# 04_Temperature.net
KiCad netlist of a schematic drawn in Altium Designer
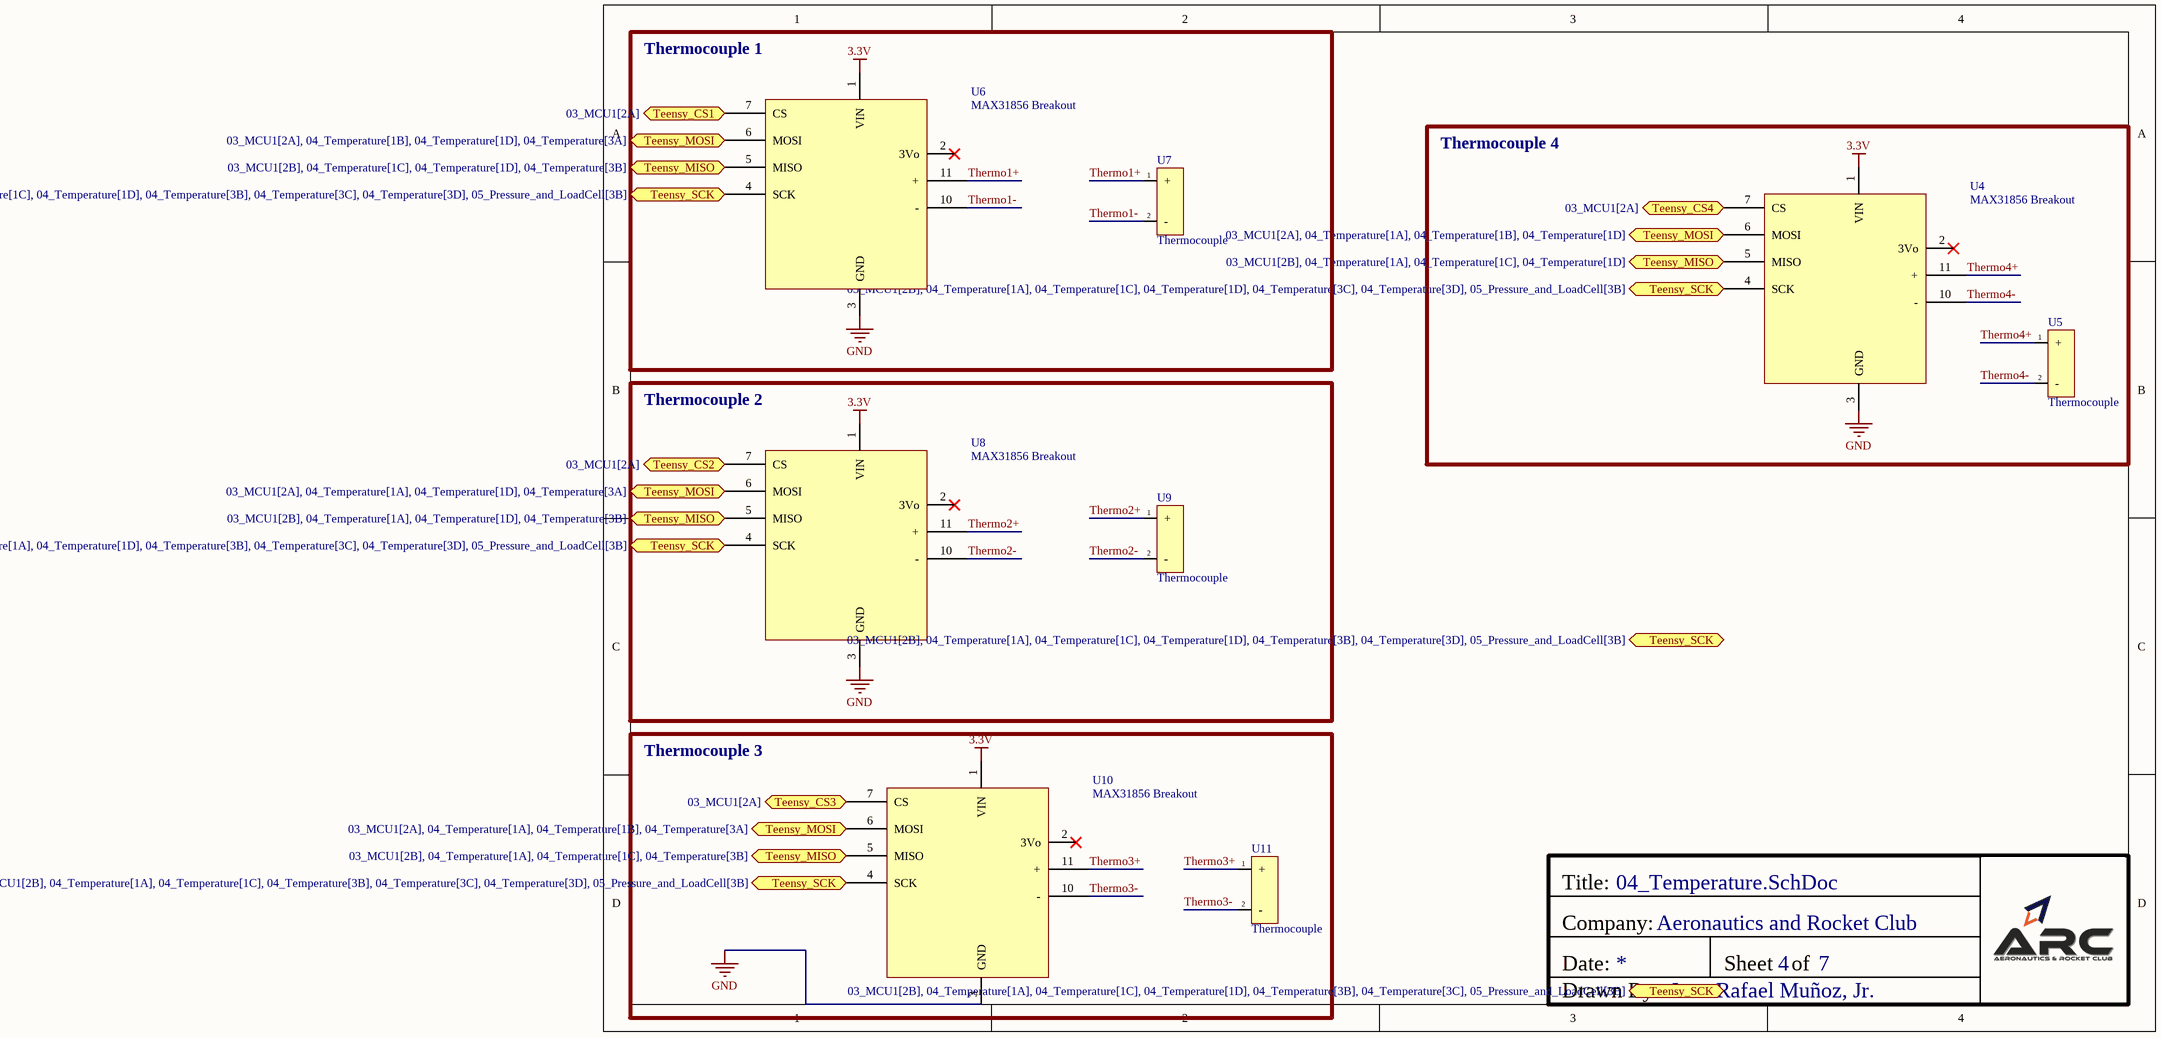
[diagram p0: 04_Temperature.SchDoc]

(export (version "E")
  (design (tool "Eeschema 10.0.6"))
  (components
    (comp (ref "U4")
      (value "MAX31856 Breakout")
      (footprint "MAX31856 Breakout")
      (libsource (lib "Ground Support_Schlib") (part "MAX31856 Breakout"))
    )
    (comp (ref "U5")
      (value "Thermocouple")
      (footprint "THERMOCOUPLE")
      (libsource (lib "Ground Support_Schlib") (part "Thermocouple"))
    )
    (comp (ref "U6")
      (value "MAX31856 Breakout")
      (footprint "MAX31856 Breakout")
      (libsource (lib "Ground Support_Schlib") (part "MAX31856 Breakout"))
    )
    (comp (ref "U7")
      (value "Thermocouple")
      (footprint "THERMOCOUPLE")
      (libsource (lib "Ground Support_Schlib") (part "Thermocouple"))
    )
    (comp (ref "U8")
      (value "MAX31856 Breakout")
      (footprint "MAX31856 Breakout")
      (libsource (lib "Ground Support_Schlib") (part "MAX31856 Breakout"))
    )
    (comp (ref "U9")
      (value "Thermocouple")
      (footprint "THERMOCOUPLE")
      (libsource (lib "Ground Support_Schlib") (part "Thermocouple"))
    )
    (comp (ref "U10")
      (value "MAX31856 Breakout")
      (footprint "MAX31856 Breakout")
      (libsource (lib "Ground Support_Schlib") (part "MAX31856 Breakout"))
    )
    (comp (ref "U11")
      (value "Thermocouple")
      (footprint "THERMOCOUPLE")
      (libsource (lib "Ground Support_Schlib") (part "Thermocouple"))
    )
  )
  (nets
    (net (code "1") (name "/Teensy_CS1") (class "Default")
      (node (ref "U6") (pin "7") (pinfunction "CS_7") (pintype "passive"))
    )
    (net (code "2") (name "/Teensy_CS2") (class "Default")
      (node (ref "U8") (pin "7") (pinfunction "CS_7") (pintype "passive"))
    )
    (net (code "3") (name "/Teensy_CS3") (class "Default")
      (node (ref "U10") (pin "7") (pinfunction "CS_7") (pintype "passive"))
    )
    (net (code "4") (name "/Teensy_CS4") (class "Default")
      (node (ref "U4") (pin "7") (pinfunction "CS_7") (pintype "passive"))
    )
    (net (code "5") (name "/Teensy_MISO") (class "Default")
      (node (ref "U10") (pin "5") (pinfunction "MISO_5") (pintype "passive"))
      (node (ref "U4") (pin "5") (pinfunction "MISO_5") (pintype "passive"))
      (node (ref "U6") (pin "5") (pinfunction "MISO_5") (pintype "passive"))
      (node (ref "U8") (pin "5") (pinfunction "MISO_5") (pintype "passive"))
    )
    (net (code "6") (name "/Teensy_MOSI") (class "Default")
      (node (ref "U10") (pin "6") (pinfunction "MOSI_6") (pintype "passive"))
      (node (ref "U4") (pin "6") (pinfunction "MOSI_6") (pintype "passive"))
      (node (ref "U6") (pin "6") (pinfunction "MOSI_6") (pintype "passive"))
      (node (ref "U8") (pin "6") (pinfunction "MOSI_6") (pintype "passive"))
    )
    (net (code "7") (name "/Teensy_SCK") (class "Default")
      (node (ref "U10") (pin "4") (pinfunction "SCK_4") (pintype "passive"))
      (node (ref "U4") (pin "4") (pinfunction "SCK_4") (pintype "passive"))
      (node (ref "U6") (pin "4") (pinfunction "SCK_4") (pintype "passive"))
      (node (ref "U8") (pin "4") (pinfunction "SCK_4") (pintype "passive"))
    )
    (net (code "8") (name "/Thermo1+") (class "Default")
      (node (ref "U6") (pin "11") (pinfunction "+_11") (pintype "passive"))
      (node (ref "U7") (pin "1") (pinfunction "+_1") (pintype "power_in"))
    )
    (net (code "9") (name "/Thermo1-") (class "Default")
      (node (ref "U6") (pin "10") (pinfunction "-_10") (pintype "passive"))
      (node (ref "U7") (pin "2") (pinfunction "-_2") (pintype "power_in"))
    )
    (net (code "10") (name "/Thermo2+") (class "Default")
      (node (ref "U8") (pin "11") (pinfunction "+_11") (pintype "passive"))
      (node (ref "U9") (pin "1") (pinfunction "+_1") (pintype "power_in"))
    )
    (net (code "11") (name "/Thermo2-") (class "Default")
      (node (ref "U8") (pin "10") (pinfunction "-_10") (pintype "passive"))
      (node (ref "U9") (pin "2") (pinfunction "-_2") (pintype "power_in"))
    )
    (net (code "12") (name "/Thermo3+") (class "Default")
      (node (ref "U10") (pin "11") (pinfunction "+_11") (pintype "passive"))
      (node (ref "U11") (pin "1") (pinfunction "+_1") (pintype "power_in"))
    )
    (net (code "13") (name "/Thermo3-") (class "Default")
      (node (ref "U10") (pin "10") (pinfunction "-_10") (pintype "passive"))
      (node (ref "U11") (pin "2") (pinfunction "-_2") (pintype "power_in"))
    )
    (net (code "14") (name "/Thermo4+") (class "Default")
      (node (ref "U4") (pin "11") (pinfunction "+_11") (pintype "passive"))
      (node (ref "U5") (pin "1") (pinfunction "+_1") (pintype "power_in"))
    )
    (net (code "15") (name "/Thermo4-") (class "Default")
      (node (ref "U4") (pin "10") (pinfunction "-_10") (pintype "passive"))
      (node (ref "U5") (pin "2") (pinfunction "-_2") (pintype "power_in"))
    )
    (net (code "16") (name "3.3V") (class "Default")
      (node (ref "U10") (pin "1") (pinfunction "VIN_1") (pintype "passive"))
      (node (ref "U4") (pin "1") (pinfunction "VIN_1") (pintype "passive"))
      (node (ref "U6") (pin "1") (pinfunction "VIN_1") (pintype "passive"))
      (node (ref "U8") (pin "1") (pinfunction "VIN_1") (pintype "passive"))
    )
    (net (code "17") (name "GND") (class "Default")
      (node (ref "U10") (pin "3") (pinfunction "GND_3") (pintype "passive"))
      (node (ref "U4") (pin "3") (pinfunction "GND_3") (pintype "passive"))
      (node (ref "U6") (pin "3") (pinfunction "GND_3") (pintype "passive"))
      (node (ref "U8") (pin "3") (pinfunction "GND_3") (pintype "passive"))
    )
    (net (code "18") (name "unconnected-(U4-3Vo-Pad2)") (class "Default")
      (node (ref "U4") (pin "2") (pinfunction "3Vo_2") (pintype "passive+no_connect"))
    )
    (net (code "19") (name "unconnected-(U6-3Vo-Pad2)") (class "Default")
      (node (ref "U6") (pin "2") (pinfunction "3Vo_2") (pintype "passive+no_connect"))
    )
    (net (code "20") (name "unconnected-(U8-3Vo-Pad2)") (class "Default")
      (node (ref "U8") (pin "2") (pinfunction "3Vo_2") (pintype "passive+no_connect"))
    )
    (net (code "21") (name "unconnected-(U10-3Vo-Pad2)") (class "Default")
      (node (ref "U10") (pin "2") (pinfunction "3Vo_2") (pintype "passive+no_connect"))
    )
  )
)
